# SD_USB.net
KiCad netlist of a schematic drawn in Altium Designer
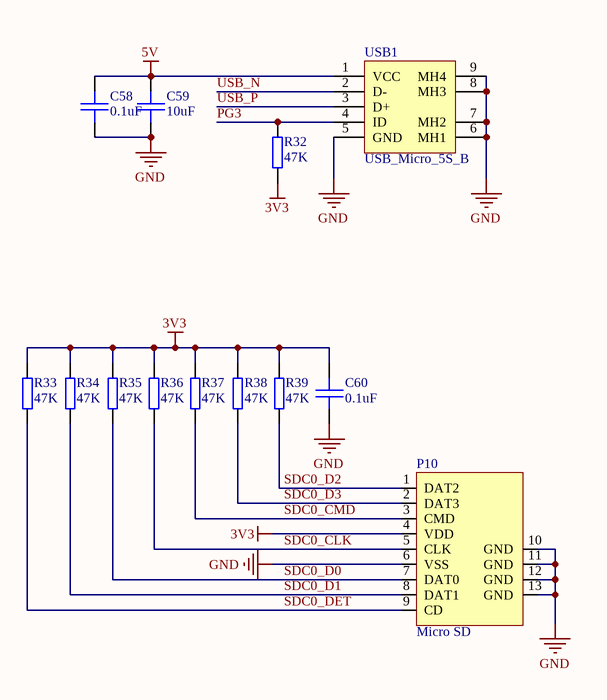
[diagram p0: SD&USB.SchDoc]

(export (version "E")
  (design (tool "Eeschema 10.0.6"))
  (components
    (comp (ref "C58")
      (value "0.1uF")
      (footprint "CAP-0603")
      (description "陶瓷贴片电容0603")
      (fields (field (name "TOLERANCE") "10%") (field (name "VOLTAGE") "50V"))
      (libsource (lib "momo") (part "C_0603"))
    )
    (comp (ref "C59")
      (value "10uF")
      (footprint "CAP-1206")
      (description "陶瓷贴片电容1206")
      (fields (field (name "TOLERANCE") "10%") (field (name "VOLTAGE") "50V"))
      (libsource (lib "momo") (part "C_1206"))
    )
    (comp (ref "C60")
      (value "0.1uF")
      (footprint "CAP-0603")
      (description "陶瓷贴片电容0603")
      (fields (field (name "TOLERANCE") "10%") (field (name "VOLTAGE") "50V"))
      (libsource (lib "momo") (part "C_0603"))
    )
    (comp (ref "P10")
      (value "Micro SD")
      (footprint "7MSDP-B0-1012")
      (description "Micro SD卡座")
      (libsource (lib "momo") (part "Micro SD"))
    )
    (comp (ref "R32")
      (value "47K")
      (footprint "RES-0603")
      (description "贴片电阻0603")
      (fields (field (name "TOLERANCE") "5%") (field (name "VOLTAGE") "50V"))
      (libsource (lib "momo") (part "R_0603"))
    )
    (comp (ref "R33")
      (value "47K")
      (footprint "RES-0603")
      (description "贴片电阻0603")
      (fields (field (name "TOLERANCE") "5%") (field (name "VOLTAGE") "50V"))
      (libsource (lib "momo") (part "R_0603"))
    )
    (comp (ref "R34")
      (value "47K")
      (footprint "RES-0603")
      (description "贴片电阻0603")
      (fields (field (name "TOLERANCE") "5%") (field (name "VOLTAGE") "50V"))
      (libsource (lib "momo") (part "R_0603"))
    )
    (comp (ref "R35")
      (value "47K")
      (footprint "RES-0603")
      (description "贴片电阻0603")
      (fields (field (name "TOLERANCE") "5%") (field (name "VOLTAGE") "50V"))
      (libsource (lib "momo") (part "R_0603"))
    )
    (comp (ref "R36")
      (value "47K")
      (footprint "RES-0603")
      (description "贴片电阻0603")
      (fields (field (name "TOLERANCE") "5%") (field (name "VOLTAGE") "50V"))
      (libsource (lib "momo") (part "R_0603"))
    )
    (comp (ref "R37")
      (value "47K")
      (footprint "RES-0603")
      (description "贴片电阻0603")
      (fields (field (name "TOLERANCE") "5%") (field (name "VOLTAGE") "50V"))
      (libsource (lib "momo") (part "R_0603"))
    )
    (comp (ref "R38")
      (value "47K")
      (footprint "RES-0603")
      (description "贴片电阻0603")
      (fields (field (name "TOLERANCE") "5%") (field (name "VOLTAGE") "50V"))
      (libsource (lib "momo") (part "R_0603"))
    )
    (comp (ref "R39")
      (value "47K")
      (footprint "RES-0603")
      (description "贴片电阻0603")
      (fields (field (name "TOLERANCE") "5%") (field (name "VOLTAGE") "50V"))
      (libsource (lib "momo") (part "R_0603"))
    )
    (comp (ref "USB1")
      (value "USB_Micro_5S_B")
      (footprint "USB_MICRO_5S_B")
      (description "micro USB母座5SB型")
      (libsource (lib "momo") (part "USB_Micro_5S_B"))
    )
  )
  (nets
    (net (code "1") (name "/PG3") (class "Default")
      (node (ref "R32") (pin "1") (pinfunction "1_1") (pintype "passive"))
      (node (ref "USB1") (pin "4") (pinfunction "ID_4") (pintype "passive"))
    )
    (net (code "2") (name "/SDC0_CLK") (class "Default")
      (node (ref "P10") (pin "5") (pinfunction "CLK_5") (pintype "passive"))
      (node (ref "R36") (pin "1") (pinfunction "1_1") (pintype "passive"))
    )
    (net (code "3") (name "/SDC0_CMD") (class "Default")
      (node (ref "P10") (pin "3") (pinfunction "CMD_3") (pintype "passive"))
      (node (ref "R37") (pin "1") (pinfunction "1_1") (pintype "passive"))
    )
    (net (code "4") (name "/SDC0_D0") (class "Default")
      (node (ref "P10") (pin "7") (pinfunction "DAT0_7") (pintype "passive"))
      (node (ref "R35") (pin "1") (pinfunction "1_1") (pintype "passive"))
    )
    (net (code "5") (name "/SDC0_D1") (class "Default")
      (node (ref "P10") (pin "8") (pinfunction "DAT1_8") (pintype "passive"))
      (node (ref "R34") (pin "1") (pinfunction "1_1") (pintype "passive"))
    )
    (net (code "6") (name "/SDC0_D2") (class "Default")
      (node (ref "P10") (pin "1") (pinfunction "DAT2_1") (pintype "passive"))
      (node (ref "R39") (pin "1") (pinfunction "1_1") (pintype "passive"))
    )
    (net (code "7") (name "/SDC0_D3") (class "Default")
      (node (ref "P10") (pin "2") (pinfunction "DAT3_2") (pintype "passive"))
      (node (ref "R38") (pin "1") (pinfunction "1_1") (pintype "passive"))
    )
    (net (code "8") (name "/SDC0_DET") (class "Default")
      (node (ref "P10") (pin "9") (pinfunction "CD_9") (pintype "passive"))
      (node (ref "R33") (pin "1") (pinfunction "1_1") (pintype "passive"))
    )
    (net (code "9") (name "/USB_N") (class "Default")
      (node (ref "USB1") (pin "2") (pinfunction "D-_2") (pintype "passive"))
    )
    (net (code "10") (name "/USB_P") (class "Default")
      (node (ref "USB1") (pin "3") (pinfunction "D+_3") (pintype "passive"))
    )
    (net (code "11") (name "3V3") (class "Default")
      (node (ref "C60") (pin "1") (pinfunction "1_1") (pintype "passive"))
      (node (ref "P10") (pin "4") (pinfunction "VDD_4") (pintype "passive"))
      (node (ref "R32") (pin "2") (pinfunction "2_2") (pintype "passive"))
      (node (ref "R33") (pin "2") (pinfunction "2_2") (pintype "passive"))
      (node (ref "R34") (pin "2") (pinfunction "2_2") (pintype "passive"))
      (node (ref "R35") (pin "2") (pinfunction "2_2") (pintype "passive"))
      (node (ref "R36") (pin "2") (pinfunction "2_2") (pintype "passive"))
      (node (ref "R37") (pin "2") (pinfunction "2_2") (pintype "passive"))
      (node (ref "R38") (pin "2") (pinfunction "2_2") (pintype "passive"))
      (node (ref "R39") (pin "2") (pinfunction "2_2") (pintype "passive"))
    )
    (net (code "12") (name "5V") (class "Default")
      (node (ref "C58") (pin "1") (pinfunction "1_1") (pintype "passive"))
      (node (ref "C59") (pin "1") (pinfunction "1_1") (pintype "passive"))
      (node (ref "USB1") (pin "1") (pinfunction "VCC_1") (pintype "power_in"))
    )
    (net (code "13") (name "GND") (class "Default")
      (node (ref "C58") (pin "2") (pinfunction "2_2") (pintype "passive"))
      (node (ref "C59") (pin "2") (pinfunction "2_2") (pintype "passive"))
      (node (ref "C60") (pin "2") (pinfunction "2_2") (pintype "passive"))
      (node (ref "P10") (pin "10") (pinfunction "GND_10") (pintype "passive"))
      (node (ref "P10") (pin "11") (pinfunction "GND_11") (pintype "passive"))
      (node (ref "P10") (pin "12") (pinfunction "GND_12") (pintype "passive"))
      (node (ref "P10") (pin "13") (pinfunction "GND_13") (pintype "passive"))
      (node (ref "P10") (pin "6") (pinfunction "VSS_6") (pintype "passive"))
      (node (ref "USB1") (pin "5") (pinfunction "GND_5") (pintype "power_in"))
      (node (ref "USB1") (pin "6") (pinfunction "MH1_6") (pintype "passive"))
      (node (ref "USB1") (pin "7") (pinfunction "MH2_7") (pintype "passive"))
      (node (ref "USB1") (pin "8") (pinfunction "MH3_8") (pintype "passive"))
      (node (ref "USB1") (pin "9") (pinfunction "MH4_9") (pintype "passive"))
    )
  )
)
